# Sheet-PT-100.net
KiCad netlist of a schematic drawn in Altium Designer
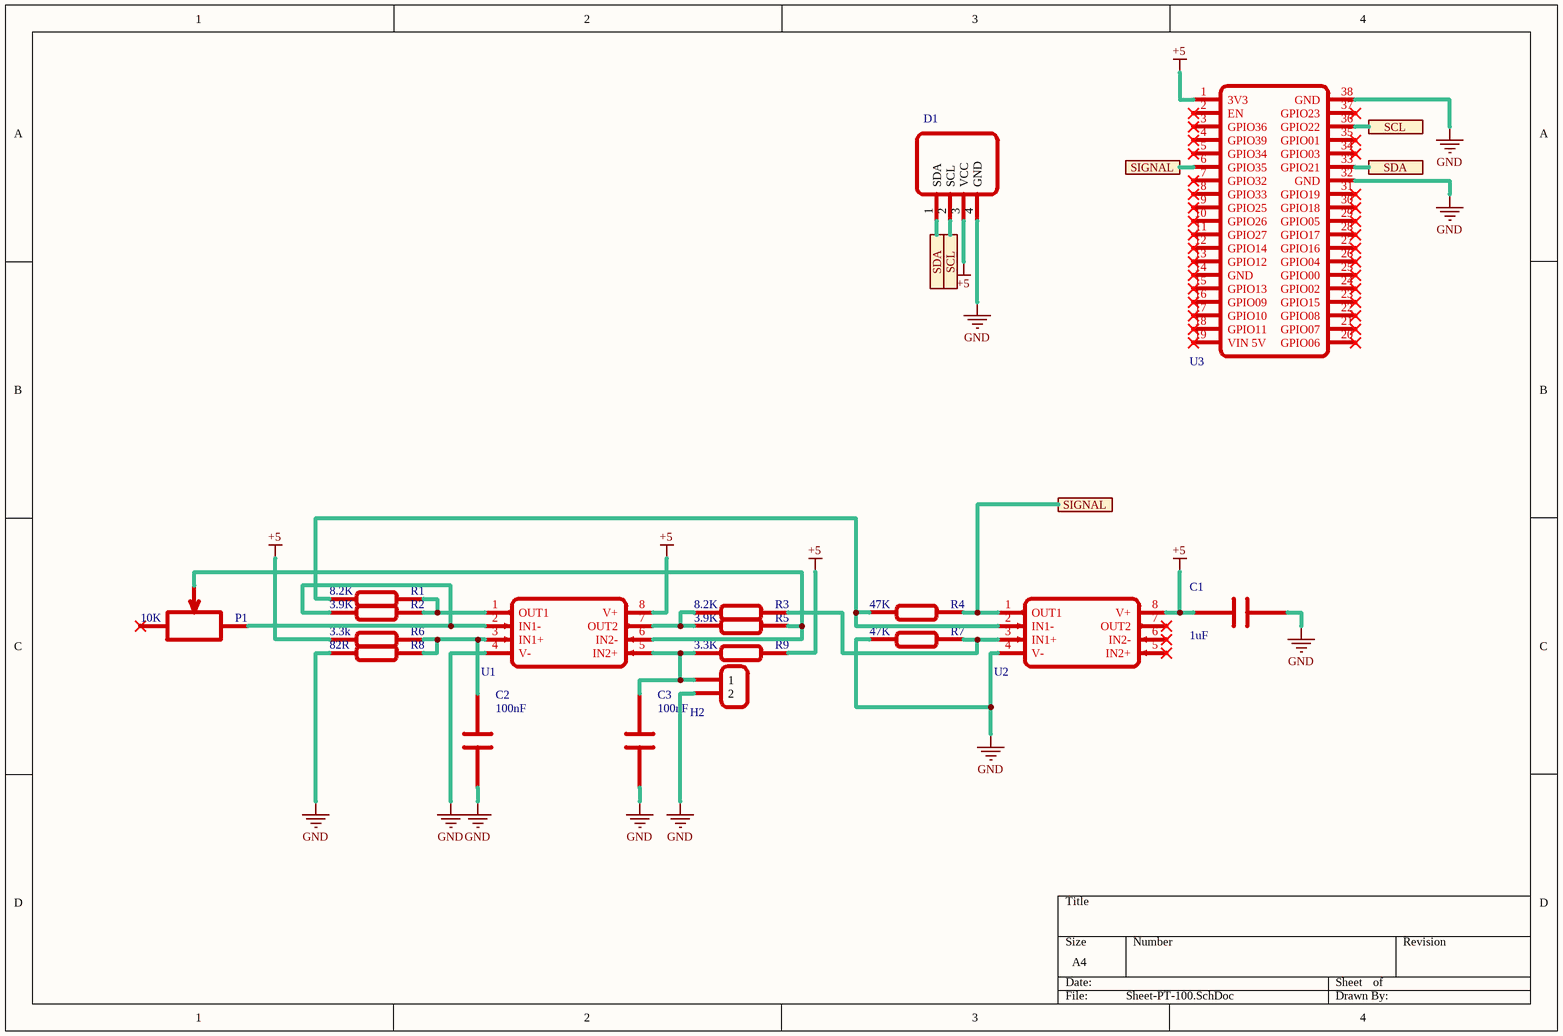
[diagram p0: Sheet-PT-100.SchDoc]

(export (version "E")
  (design (tool "Eeschema 10.0.6"))
  (components
    (comp (ref "C1")
      (value "1uF")
      (footprint "Cap-Rad-Cer-D3.5-L1.5-P2.5")
      (description "Ceramic Capacitor")
      (libsource (lib "CTAI-Library") (part "CAP-CER"))
    )
    (comp (ref "C2")
      (value "100nF")
      (footprint "Cap-Rad-Cer-D3.5-L1.5-P2.5")
      (description "Ceramic Capacitor")
      (libsource (lib "CTAI-Library") (part "CAP-CER"))
    )
    (comp (ref "C3")
      (value "100nF")
      (footprint "Cap-Rad-Cer-D3.5-L1.5-P2.5")
      (description "Ceramic Capacitor")
      (libsource (lib "CTAI-Library") (part "CAP-CER"))
    )
    (comp (ref "D1")
      (value "SSD1306-0.96-128X32-I2C")
      (footprint "SSD1306-0.96-12832-I2C")
      (description "SSD1306-0.96inch 128X32 I2C 4P")
      (libsource (lib "CTAI-Library") (part "SSD1306-0.96-128X32-I2C"))
    )
    (comp (ref "H2")
      (value "CONN-2P")
      (footprint "HDR-M-2.54-2P")
      (description "Connector 2 Pole")
      (libsource (lib "CTAI-Library") (part "CONN-2P"))
    )
    (comp (ref "P1")
      (value "10K")
      (footprint "3296X")
      (description "Potentionmeter")
      (libsource (lib "CTAI-Library") (part "3296x"))
    )
    (comp (ref "R1")
      (value "8.2K")
      (footprint "Res Axial 0.3")
      (description "Resistor")
      (libsource (lib "CTAI-Library") (part "Resistor"))
    )
    (comp (ref "R2")
      (value "3.9K")
      (footprint "Res Axial 0.3 Vertical")
      (description "Resistor")
      (libsource (lib "CTAI-Library") (part "Resistor"))
    )
    (comp (ref "R3")
      (value "8.2K")
      (footprint "Res Axial 0.3")
      (description "Resistor")
      (libsource (lib "CTAI-Library") (part "Resistor"))
    )
    (comp (ref "R4")
      (value "47K")
      (footprint "Res Axial 0.3 Vertical")
      (description "Resistor")
      (libsource (lib "CTAI-Library") (part "Resistor"))
    )
    (comp (ref "R5")
      (value "3.9K")
      (footprint "Res Axial 0.3 Vertical")
      (description "Resistor")
      (libsource (lib "CTAI-Library") (part "Resistor"))
    )
    (comp (ref "R6")
      (value "3.3k")
      (footprint "Res Axial 0.3")
      (description "Resistor")
      (libsource (lib "CTAI-Library") (part "Resistor"))
    )
    (comp (ref "R7")
      (value "47K")
      (footprint "Res Axial 0.3 Vertical")
      (description "Resistor")
      (libsource (lib "CTAI-Library") (part "Resistor"))
    )
    (comp (ref "R8")
      (value "82R")
      (footprint "Res Axial 0.3")
      (description "Resistor")
      (libsource (lib "CTAI-Library") (part "Resistor"))
    )
    (comp (ref "R9")
      (value "3.3K")
      (footprint "Res Axial 0.3")
      (description "Resistor")
      (libsource (lib "CTAI-Library") (part "Resistor"))
    )
    (comp (ref "U1")
      (value "LM358")
      (footprint "DIP8")
      (description "Low-power dual Operational Amplifier")
      (libsource (lib "CTAI-Library") (part "LM358"))
    )
    (comp (ref "U2")
      (value "LM358")
      (footprint "DIP8")
      (description "Low-power dual Operational Amplifier")
      (libsource (lib "CTAI-Library") (part "LM358"))
    )
    (comp (ref "U3")
      (value "ESP32-DEV-KIT")
      (footprint "ESP32-WROOM-32-38PIN")
      (description "ESP32 Dev Kit module 38 Pin")
      (libsource (lib "CTAI-Library") (part "ESP32-DEVKIT"))
    )
  )
  (nets
    (net (code "1") (name "+5") (class "Default")
      (node (ref "C1") (pin "1") (pintype "passive"))
      (node (ref "D1") (pin "3") (pinfunction "VCC_3") (pintype "passive"))
      (node (ref "R6") (pin "1") (pinfunction "1_1") (pintype "passive"))
      (node (ref "R9") (pin "2") (pinfunction "2_2") (pintype "passive"))
      (node (ref "U1") (pin "8") (pinfunction "V+_8") (pintype "passive"))
      (node (ref "U2") (pin "8") (pinfunction "V+_8") (pintype "passive"))
      (node (ref "U3") (pin "1") (pinfunction "3V3_1") (pintype "passive"))
    )
    (net (code "2") (name "/SCL") (class "Default")
      (node (ref "D1") (pin "2") (pinfunction "SCL_2") (pintype "passive"))
      (node (ref "U3") (pin "36") (pinfunction "GPIO22_36") (pintype "passive"))
    )
    (net (code "3") (name "/SDA") (class "Default")
      (node (ref "D1") (pin "1") (pinfunction "SDA_1") (pintype "passive"))
      (node (ref "U3") (pin "33") (pinfunction "GPIO21_33") (pintype "passive"))
    )
    (net (code "4") (name "/SIGNAL") (class "Default")
      (node (ref "R4") (pin "1") (pinfunction "1_1") (pintype "passive"))
      (node (ref "U2") (pin "1") (pinfunction "OUT1_1") (pintype "output"))
      (node (ref "U3") (pin "6") (pinfunction "GPIO35_6") (pintype "passive"))
    )
    (net (code "5") (name "GND") (class "Default")
      (node (ref "C1") (pin "2") (pintype "passive"))
      (node (ref "C2") (pin "1") (pintype "passive"))
      (node (ref "C3") (pin "1") (pintype "passive"))
      (node (ref "D1") (pin "4") (pinfunction "GND_4") (pintype "passive"))
      (node (ref "H2") (pin "2") (pinfunction "2_2") (pintype "passive"))
      (node (ref "R7") (pin "2") (pinfunction "2_2") (pintype "passive"))
      (node (ref "R8") (pin "1") (pinfunction "1_1") (pintype "passive"))
      (node (ref "U1") (pin "4") (pinfunction "V-_4") (pintype "passive"))
      (node (ref "U2") (pin "4") (pinfunction "V-_4") (pintype "passive"))
      (node (ref "U3") (pin "32") (pinfunction "GND_32") (pintype "passive"))
      (node (ref "U3") (pin "38") (pinfunction "GND_38") (pintype "passive"))
    )
    (net (code "6") (name "Net-(U1-IN1+)") (class "Default")
      (node (ref "C2") (pin "2") (pintype "passive"))
      (node (ref "R6") (pin "2") (pinfunction "2_2") (pintype "passive"))
      (node (ref "R8") (pin "2") (pinfunction "2_2") (pintype "passive"))
      (node (ref "U1") (pin "3") (pinfunction "IN1+_3") (pintype "input"))
    )
    (net (code "7") (name "Net-(U1-IN1-)") (class "Default")
      (node (ref "P1") (pin "3") (pintype "passive"))
      (node (ref "R2") (pin "1") (pinfunction "1_1") (pintype "passive"))
      (node (ref "U1") (pin "2") (pinfunction "IN1-_2") (pintype "input"))
    )
    (net (code "8") (name "Net-(U1-IN2+)") (class "Default")
      (node (ref "C3") (pin "2") (pintype "passive"))
      (node (ref "H2") (pin "1") (pinfunction "1_1") (pintype "passive"))
      (node (ref "R9") (pin "1") (pinfunction "1_1") (pintype "passive"))
      (node (ref "U1") (pin "5") (pinfunction "IN2+_5") (pintype "input"))
    )
    (net (code "9") (name "Net-(U1-IN2-)") (class "Default")
      (node (ref "P1") (pin "2") (pinfunction "2_2") (pintype "input"))
      (node (ref "R5") (pin "1") (pinfunction "1_1") (pintype "passive"))
      (node (ref "U1") (pin "6") (pinfunction "IN2-_6") (pintype "input"))
    )
    (net (code "10") (name "Net-(U1-OUT1)") (class "Default")
      (node (ref "R1") (pin "2") (pinfunction "2_2") (pintype "passive"))
      (node (ref "R2") (pin "2") (pinfunction "2_2") (pintype "passive"))
      (node (ref "U1") (pin "1") (pinfunction "OUT1_1") (pintype "output"))
    )
    (net (code "11") (name "Net-(U1-OUT2)") (class "Default")
      (node (ref "R3") (pin "1") (pinfunction "1_1") (pintype "passive"))
      (node (ref "R5") (pin "2") (pinfunction "2_2") (pintype "passive"))
      (node (ref "U1") (pin "7") (pinfunction "OUT2_7") (pintype "output"))
    )
    (net (code "12") (name "Net-(U2-IN1+)") (class "Default")
      (node (ref "R3") (pin "2") (pinfunction "2_2") (pintype "passive"))
      (node (ref "R7") (pin "1") (pinfunction "1_1") (pintype "passive"))
      (node (ref "U2") (pin "3") (pinfunction "IN1+_3") (pintype "input"))
    )
    (net (code "13") (name "Net-(U2-IN1-)") (class "Default")
      (node (ref "R1") (pin "1") (pinfunction "1_1") (pintype "passive"))
      (node (ref "R4") (pin "2") (pinfunction "2_2") (pintype "passive"))
      (node (ref "U2") (pin "2") (pinfunction "IN1-_2") (pintype "input"))
    )
    (net (code "14") (name "unconnected-(P1-Pad1)") (class "Default")
      (node (ref "P1") (pin "1") (pintype "passive+no_connect"))
    )
    (net (code "15") (name "unconnected-(U2-IN2+-Pad5)") (class "Default")
      (node (ref "U2") (pin "5") (pinfunction "IN2+_5") (pintype "input+no_connect"))
    )
    (net (code "16") (name "unconnected-(U2-IN2--Pad6)") (class "Default")
      (node (ref "U2") (pin "6") (pinfunction "IN2-_6") (pintype "input+no_connect"))
    )
    (net (code "17") (name "unconnected-(U2-OUT2-Pad7)") (class "Default")
      (node (ref "U2") (pin "7") (pinfunction "OUT2_7") (pintype "output+no_connect"))
    )
    (net (code "18") (name "unconnected-(U3-EN-Pad2)") (class "Default")
      (node (ref "U3") (pin "2") (pinfunction "EN_2") (pintype "passive+no_connect"))
    )
    (net (code "19") (name "unconnected-(U3-GND-Pad14)") (class "Default")
      (node (ref "U3") (pin "14") (pinfunction "GND_14") (pintype "passive+no_connect"))
    )
    (net (code "20") (name "unconnected-(U3-GPIO00-Pad25)") (class "Default")
      (node (ref "U3") (pin "25") (pinfunction "GPIO00_25") (pintype "passive+no_connect"))
    )
    (net (code "21") (name "unconnected-(U3-GPIO01-Pad35)") (class "Default")
      (node (ref "U3") (pin "35") (pinfunction "GPIO01_35") (pintype "passive+no_connect"))
    )
    (net (code "22") (name "unconnected-(U3-GPIO02-Pad24)") (class "Default")
      (node (ref "U3") (pin "24") (pinfunction "GPIO02_24") (pintype "passive+no_connect"))
    )
    (net (code "23") (name "unconnected-(U3-GPIO03-Pad34)") (class "Default")
      (node (ref "U3") (pin "34") (pinfunction "GPIO03_34") (pintype "passive+no_connect"))
    )
    (net (code "24") (name "unconnected-(U3-GPIO04-Pad26)") (class "Default")
      (node (ref "U3") (pin "26") (pinfunction "GPIO04_26") (pintype "passive+no_connect"))
    )
    (net (code "25") (name "unconnected-(U3-GPIO05-Pad29)") (class "Default")
      (node (ref "U3") (pin "29") (pinfunction "GPIO05_29") (pintype "passive+no_connect"))
    )
    (net (code "26") (name "unconnected-(U3-GPIO06-Pad20)") (class "Default")
      (node (ref "U3") (pin "20") (pinfunction "GPIO06_20") (pintype "passive+no_connect"))
    )
    (net (code "27") (name "unconnected-(U3-GPIO07-Pad21)") (class "Default")
      (node (ref "U3") (pin "21") (pinfunction "GPIO07_21") (pintype "passive+no_connect"))
    )
    (net (code "28") (name "unconnected-(U3-GPIO08-Pad22)") (class "Default")
      (node (ref "U3") (pin "22") (pinfunction "GPIO08_22") (pintype "passive+no_connect"))
    )
    (net (code "29") (name "unconnected-(U3-GPIO09-Pad16)") (class "Default")
      (node (ref "U3") (pin "16") (pinfunction "GPIO09_16") (pintype "passive+no_connect"))
    )
    (net (code "30") (name "unconnected-(U3-GPIO10-Pad17)") (class "Default")
      (node (ref "U3") (pin "17") (pinfunction "GPIO10_17") (pintype "passive+no_connect"))
    )
    (net (code "31") (name "unconnected-(U3-GPIO11-Pad18)") (class "Default")
      (node (ref "U3") (pin "18") (pinfunction "GPIO11_18") (pintype "passive+no_connect"))
    )
    (net (code "32") (name "unconnected-(U3-GPIO12-Pad13)") (class "Default")
      (node (ref "U3") (pin "13") (pinfunction "GPIO12_13") (pintype "passive+no_connect"))
    )
    (net (code "33") (name "unconnected-(U3-GPIO13-Pad15)") (class "Default")
      (node (ref "U3") (pin "15") (pinfunction "GPIO13_15") (pintype "passive+no_connect"))
    )
    (net (code "34") (name "unconnected-(U3-GPIO14-Pad12)") (class "Default")
      (node (ref "U3") (pin "12") (pinfunction "GPIO14_12") (pintype "passive+no_connect"))
    )
    (net (code "35") (name "unconnected-(U3-GPIO15-Pad23)") (class "Default")
      (node (ref "U3") (pin "23") (pinfunction "GPIO15_23") (pintype "passive+no_connect"))
    )
    (net (code "36") (name "unconnected-(U3-GPIO16-Pad27)") (class "Default")
      (node (ref "U3") (pin "27") (pinfunction "GPIO16_27") (pintype "passive+no_connect"))
    )
    (net (code "37") (name "unconnected-(U3-GPIO17-Pad28)") (class "Default")
      (node (ref "U3") (pin "28") (pinfunction "GPIO17_28") (pintype "passive+no_connect"))
    )
    (net (code "38") (name "unconnected-(U3-GPIO18-Pad30)") (class "Default")
      (node (ref "U3") (pin "30") (pinfunction "GPIO18_30") (pintype "passive+no_connect"))
    )
    (net (code "39") (name "unconnected-(U3-GPIO19-Pad31)") (class "Default")
      (node (ref "U3") (pin "31") (pinfunction "GPIO19_31") (pintype "passive+no_connect"))
    )
    (net (code "40") (name "unconnected-(U3-GPIO23-Pad37)") (class "Default")
      (node (ref "U3") (pin "37") (pinfunction "GPIO23_37") (pintype "passive+no_connect"))
    )
    (net (code "41") (name "unconnected-(U3-GPIO25-Pad9)") (class "Default")
      (node (ref "U3") (pin "9") (pinfunction "GPIO25_9") (pintype "passive+no_connect"))
    )
    (net (code "42") (name "unconnected-(U3-GPIO26-Pad10)") (class "Default")
      (node (ref "U3") (pin "10") (pinfunction "GPIO26_10") (pintype "passive+no_connect"))
    )
    (net (code "43") (name "unconnected-(U3-GPIO27-Pad11)") (class "Default")
      (node (ref "U3") (pin "11") (pinfunction "GPIO27_11") (pintype "passive+no_connect"))
    )
    (net (code "44") (name "unconnected-(U3-GPIO32-Pad7)") (class "Default")
      (node (ref "U3") (pin "7") (pinfunction "GPIO32_7") (pintype "passive+no_connect"))
    )
    (net (code "45") (name "unconnected-(U3-GPIO33-Pad8)") (class "Default")
      (node (ref "U3") (pin "8") (pinfunction "GPIO33_8") (pintype "passive+no_connect"))
    )
    (net (code "46") (name "unconnected-(U3-GPIO34-Pad5)") (class "Default")
      (node (ref "U3") (pin "5") (pinfunction "GPIO34_5") (pintype "passive+no_connect"))
    )
    (net (code "47") (name "unconnected-(U3-GPIO36-Pad3)") (class "Default")
      (node (ref "U3") (pin "3") (pinfunction "GPIO36_3") (pintype "passive+no_connect"))
    )
    (net (code "48") (name "unconnected-(U3-GPIO39-Pad4)") (class "Default")
      (node (ref "U3") (pin "4") (pinfunction "GPIO39_4") (pintype "passive+no_connect"))
    )
    (net (code "49") (name "unconnected-(U3-VIN_5V-Pad19)") (class "Default")
      (node (ref "U3") (pin "19") (pinfunction "VIN_5V_19") (pintype "passive+no_connect"))
    )
  )
)
